# 007_Parallel_operation.net
KiCad netlist of a schematic drawn in Altium Designer
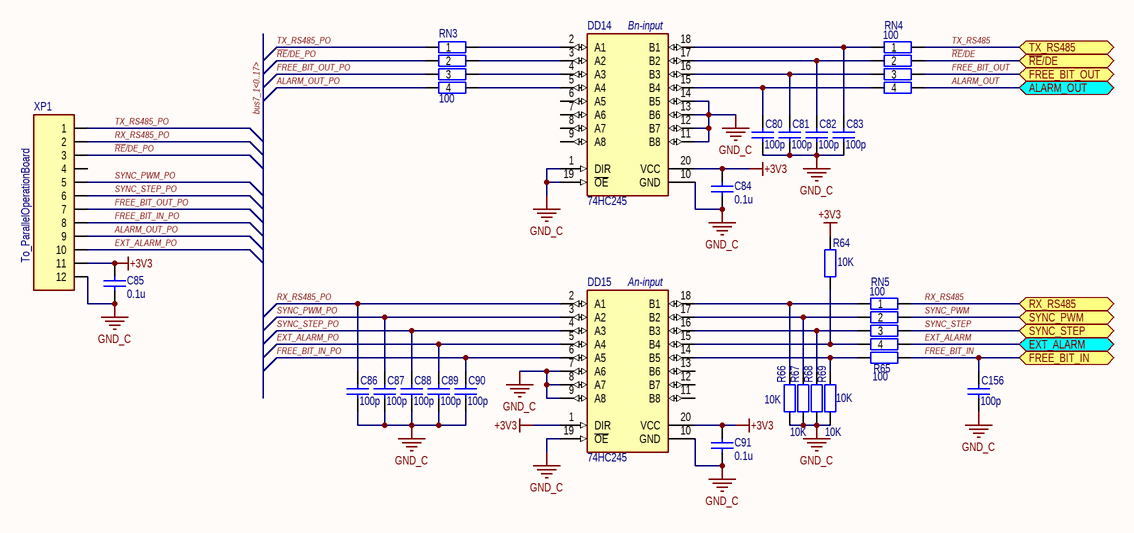
[diagram p0: 007_Parallel_operation.SchDoc]

(export (version "E")
  (design (tool "Eeschema 10.0.6"))
  (components
    (comp (ref "C80")
      (value "100p")
      (footprint "mainLib:SMD_C_0603")
      (description "SMD C 0603 MURATA 100V 5% NP0")
      (fields (field (name "PARTNUMBER") "GRM1885C2A101JA01") (field (name "MANUFACTURER") "MURATA"))
      (libsource (lib "mainRCLib") (part "C0603 100p 100V 5%"))
    )
    (comp (ref "C81")
      (value "100p")
      (footprint "mainLib:SMD_C_0603")
      (description "SMD C 0603 MURATA 100V 5% NP0")
      (fields (field (name "PARTNUMBER") "GRM1885C2A101JA01") (field (name "MANUFACTURER") "MURATA"))
      (libsource (lib "mainRCLib") (part "C0603 100p 100V 5%"))
    )
    (comp (ref "C82")
      (value "100p")
      (footprint "mainLib:SMD_C_0603")
      (description "SMD C 0603 MURATA 100V 5% NP0")
      (fields (field (name "PARTNUMBER") "GRM1885C2A101JA01") (field (name "MANUFACTURER") "MURATA"))
      (libsource (lib "mainRCLib") (part "C0603 100p 100V 5%"))
    )
    (comp (ref "C83")
      (value "100p")
      (footprint "mainLib:SMD_C_0603")
      (description "SMD C 0603 MURATA 100V 5% NP0")
      (fields (field (name "PARTNUMBER") "GRM1885C2A101JA01") (field (name "MANUFACTURER") "MURATA"))
      (libsource (lib "mainRCLib") (part "C0603 100p 100V 5%"))
    )
    (comp (ref "C84")
      (value "0.1u")
      (footprint "mainLib:SMD_C_0603")
      (description "SMD C 0603 MURATA 50V 10% X7R")
      (fields (field (name "PARTNUMBER") "GRM188R71H104K") (field (name "MANUFACTURER") "MURATA"))
      (libsource (lib "mainRCLib") (part "C0603 0.1u 50V 10%"))
    )
    (comp (ref "C85")
      (value "0.1u")
      (footprint "mainLib:SMD_C_0603")
      (description "SMD C 0603 MURATA 50V 10% X7R")
      (fields (field (name "PARTNUMBER") "GRM188R71H104K") (field (name "MANUFACTURER") "MURATA"))
      (libsource (lib "mainRCLib") (part "C0603 0.1u 50V 10%"))
    )
    (comp (ref "C86")
      (value "100p")
      (footprint "mainLib:SMD_C_0603")
      (description "SMD C 0603 MURATA 100V 5% NP0")
      (fields (field (name "PARTNUMBER") "GRM1885C2A101JA01") (field (name "MANUFACTURER") "MURATA"))
      (libsource (lib "mainRCLib") (part "C0603 100p 100V 5%"))
    )
    (comp (ref "C87")
      (value "100p")
      (footprint "mainLib:SMD_C_0603")
      (description "SMD C 0603 MURATA 100V 5% NP0")
      (fields (field (name "PARTNUMBER") "GRM1885C2A101JA01") (field (name "MANUFACTURER") "MURATA"))
      (libsource (lib "mainRCLib") (part "C0603 100p 100V 5%"))
    )
    (comp (ref "C88")
      (value "100p")
      (footprint "mainLib:SMD_C_0603")
      (description "SMD C 0603 MURATA 100V 5% NP0")
      (fields (field (name "PARTNUMBER") "GRM1885C2A101JA01") (field (name "MANUFACTURER") "MURATA"))
      (libsource (lib "mainRCLib") (part "C0603 100p 100V 5%"))
    )
    (comp (ref "C89")
      (value "100p")
      (footprint "mainLib:SMD_C_0603")
      (description "SMD C 0603 MURATA 100V 5% NP0")
      (fields (field (name "PARTNUMBER") "GRM1885C2A101JA01") (field (name "MANUFACTURER") "MURATA"))
      (libsource (lib "mainRCLib") (part "C0603 100p 100V 5%"))
    )
    (comp (ref "C90")
      (value "100p")
      (footprint "mainLib:SMD_C_0603")
      (description "SMD C 0603 MURATA 100V 5% NP0")
      (fields (field (name "PARTNUMBER") "GRM1885C2A101JA01") (field (name "MANUFACTURER") "MURATA"))
      (libsource (lib "mainRCLib") (part "C0603 100p 100V 5%"))
    )
    (comp (ref "C91")
      (value "0.1u")
      (footprint "mainLib:SMD_C_0603")
      (description "SMD C 0603 MURATA 50V 10% X7R")
      (fields (field (name "PARTNUMBER") "GRM188R71H104K") (field (name "MANUFACTURER") "MURATA"))
      (libsource (lib "mainRCLib") (part "C0603 0.1u 50V 10%"))
    )
    (comp (ref "C156")
      (value "100p")
      (footprint "mainLib:SMD_C_0603")
      (description "SMD C 0603 MURATA 100V 5% NP0")
      (fields (field (name "PARTNUMBER") "GRM1885C2A101JA01") (field (name "MANUFACTURER") "MURATA"))
      (libsource (lib "mainRCLib") (part "C0603 100p 100V 5%"))
    )
    (comp (ref "DD14")
      (value "74HC245")
      (footprint "mainLib:TSSOP20")
      (description "Octal Bus Transceivers With 3-State Outputs, PW0020A")
      (fields (field (name "MANUFACTURER") "Texas Instruments") (field (name "PARTNUMBER") "74HC245PW"))
      (libsource (lib "mainLib") (part "74HC245"))
    )
    (comp (ref "DD15")
      (value "74HC245")
      (footprint "mainLib:TSSOP20")
      (description "Octal Bus Transceivers With 3-State Outputs, PW0020A")
      (fields (field (name "MANUFACTURER") "Texas Instruments") (field (name "PARTNUMBER") "SN74HC245PW"))
      (libsource (lib "mainLib") (part "74HC245"))
    )
    (comp (ref "R64")
      (value "10K")
      (footprint "SMD_R_0603")
      (description "SMD R 0603 VISHAY 0.1W 75V 1% 100ppm")
      (fields (field (name "PARTNUMBER") "CRCW060310K0FK") (field (name "MANUFACTURER") "VISHAY"))
      (libsource (lib "mainRCLib") (part "R0603 10К 1%"))
    )
    (comp (ref "R65")
      (value "100")
      (footprint "SMD_R_0603")
      (description "SMD R 0603 VISHAY 0.1W 75V 1% 100ppm")
      (fields (field (name "PARTNUMBER") "CRCW0603100RFK") (field (name "MANUFACTURER") "VISHAY"))
      (libsource (lib "mainRCLib") (part "R0603 100 1%"))
    )
    (comp (ref "R66")
      (value "10K")
      (footprint "SMD_R_0603")
      (description "SMD R 0603 VISHAY 0.1W 75V 1% 100ppm")
      (fields (field (name "PARTNUMBER") "CRCW060310K0FK") (field (name "MANUFACTURER") "VISHAY"))
      (libsource (lib "mainRCLib") (part "R0603 10К 1%"))
    )
    (comp (ref "R67")
      (value "10K")
      (footprint "SMD_R_0603")
      (description "SMD R 0603 VISHAY 0.1W 75V 1% 100ppm")
      (fields (field (name "PARTNUMBER") "CRCW060310K0FK") (field (name "MANUFACTURER") "VISHAY"))
      (libsource (lib "mainRCLib") (part "R0603 10К 1%"))
    )
    (comp (ref "R68")
      (value "10K")
      (footprint "SMD_R_0603")
      (description "SMD R 0603 VISHAY 0.1W 75V 1% 100ppm")
      (fields (field (name "PARTNUMBER") "CRCW060310K0FK") (field (name "MANUFACTURER") "VISHAY"))
      (libsource (lib "mainRCLib") (part "R0603 10К 1%"))
    )
    (comp (ref "R69")
      (value "10K")
      (footprint "SMD_R_0603")
      (description "SMD R 0603 VISHAY 0.1W 75V 1% 100ppm")
      (fields (field (name "PARTNUMBER") "CRCW060310K0FK") (field (name "MANUFACTURER") "VISHAY"))
      (libsource (lib "mainRCLib") (part "R0603 10К 1%"))
    )
    (comp (ref "RN3")
      (value "100")
      (footprint "mainLib:CRA06S")
      (description "SMD RESISTOR ARRAY VISHAY 0.063W 50V 1% 100ppm")
      (fields (field (name "PARTNUMBER") "CRA06S083100RF") (field (name "MANUFACTURER") "VISHAY"))
      (libsource (lib "mainRCLib") (part "CRA06S 4x100 1%"))
    )
    (comp (ref "RN4")
      (value "100")
      (footprint "mainLib:CRA06S")
      (description "SMD RESISTOR ARRAY VISHAY 0.063W 50V 1% 100ppm")
      (fields (field (name "PARTNUMBER") "CRA06S083100RF") (field (name "MANUFACTURER") "VISHAY"))
      (libsource (lib "mainRCLib") (part "CRA06S 4x100 1%"))
    )
    (comp (ref "RN5")
      (value "100")
      (footprint "mainLib:CRA06S")
      (description "SMD RESISTOR ARRAY VISHAY 0.063W 50V 1% 100ppm")
      (fields (field (name "PARTNUMBER") "CRA06S083100RF") (field (name "MANUFACTURER") "VISHAY"))
      (libsource (lib "mainRCLib") (part "CRA06S 4x100 1%"))
    )
    (comp (ref "XP1")
      (value "То_ParallelOperationBoard")
      (footprint "mainLib:XP(ParallelOperation)")
      (description "to ParallelOperationBoard")
      (fields (field (name "PARTNUMBER") "R100.20.62.10.00") (field (name "MANUFACTURER") "OLTEST"))
      (libsource (lib "mainLib") (part "Plata_ParallelOperation"))
    )
  )
  (nets
    (net (code "2") (name "+3V3") (class "Default")
      (node (ref "C84") (pin "2") (pinfunction "2_2") (pintype "passive"))
      (node (ref "C85") (pin "2") (pinfunction "2_2") (pintype "passive"))
      (node (ref "C91") (pin "2") (pinfunction "2_2") (pintype "passive"))
      (node (ref "DD14") (pin "20") (pinfunction "VCC_20") (pintype "power_in"))
      (node (ref "DD15") (pin "1") (pinfunction "DIR_1") (pintype "input"))
      (node (ref "DD15") (pin "20") (pinfunction "VCC_20") (pintype "power_in"))
      (node (ref "R64") (pin "2") (pinfunction "2_2") (pintype "passive"))
      (node (ref "XP1") (pin "11") (pinfunction "11_11") (pintype "passive"))
    )
    (net (code "3") (name "/ALARM_OUT") (class "Default")
      (node (ref "RN4") (pin "5") (pinfunction "5_5") (pintype "passive"))
    )
    (net (code "4") (name "/ALARM_OUT_PO") (class "Default")
      (node (ref "RN3") (pin "4") (pinfunction "4_4") (pintype "passive"))
      (node (ref "XP1") (pin "9") (pinfunction "9_9") (pintype "passive"))
    )
    (net (code "5") (name "/EXT_ALARM") (class "Default")
      (node (ref "RN5") (pin "5") (pinfunction "5_5") (pintype "passive"))
    )
    (net (code "6") (name "/EXT_ALARM_PO") (class "Default")
      (node (ref "C89") (pin "2") (pinfunction "2_2") (pintype "passive"))
      (node (ref "DD15") (pin "5") (pinfunction "A4_5") (pintype "bidirectional"))
      (node (ref "XP1") (pin "10") (pinfunction "10_10") (pintype "passive"))
    )
    (net (code "7") (name "/FREE_BIT_IN") (class "Default")
      (node (ref "C156") (pin "2") (pinfunction "2_2") (pintype "passive"))
      (node (ref "R65") (pin "2") (pinfunction "2_2") (pintype "passive"))
    )
    (net (code "8") (name "/FREE_BIT_IN_PO") (class "Default")
      (node (ref "C90") (pin "2") (pinfunction "2_2") (pintype "passive"))
      (node (ref "DD15") (pin "6") (pinfunction "A5_6") (pintype "bidirectional"))
      (node (ref "XP1") (pin "8") (pinfunction "8_8") (pintype "passive"))
    )
    (net (code "9") (name "/FREE_BIT_OUT") (class "Default")
      (node (ref "RN4") (pin "6") (pinfunction "6_6") (pintype "passive"))
    )
    (net (code "10") (name "/FREE_BIT_OUT_PO") (class "Default")
      (node (ref "RN3") (pin "3") (pinfunction "3_3") (pintype "passive"))
      (node (ref "XP1") (pin "7") (pinfunction "7_7") (pintype "passive"))
    )
    (net (code "11") (name "/RX_RS485") (class "Default")
      (node (ref "RN5") (pin "8") (pinfunction "8_8") (pintype "passive"))
    )
    (net (code "12") (name "/RX_RS485_PO") (class "Default")
      (node (ref "C86") (pin "2") (pinfunction "2_2") (pintype "passive"))
      (node (ref "DD15") (pin "2") (pinfunction "A1_2") (pintype "bidirectional"))
      (node (ref "XP1") (pin "2") (pinfunction "2_2") (pintype "passive"))
    )
    (net (code "13") (name "/SYNC_PWM") (class "Default")
      (node (ref "RN5") (pin "7") (pinfunction "7_7") (pintype "passive"))
    )
    (net (code "14") (name "/SYNC_PWM_PO") (class "Default")
      (node (ref "C87") (pin "2") (pinfunction "2_2") (pintype "passive"))
      (node (ref "DD15") (pin "3") (pinfunction "A2_3") (pintype "bidirectional"))
      (node (ref "XP1") (pin "5") (pinfunction "5_5") (pintype "passive"))
    )
    (net (code "15") (name "/SYNC_STEP") (class "Default")
      (node (ref "RN5") (pin "6") (pinfunction "6_6") (pintype "passive"))
    )
    (net (code "16") (name "/SYNC_STEP_PO") (class "Default")
      (node (ref "C88") (pin "2") (pinfunction "2_2") (pintype "passive"))
      (node (ref "DD15") (pin "4") (pinfunction "A3_4") (pintype "bidirectional"))
      (node (ref "XP1") (pin "6") (pinfunction "6_6") (pintype "passive"))
    )
    (net (code "17") (name "/TX_RS485") (class "Default")
      (node (ref "RN4") (pin "8") (pinfunction "8_8") (pintype "passive"))
    )
    (net (code "18") (name "/TX_RS485_PO") (class "Default")
      (node (ref "RN3") (pin "1") (pinfunction "1_1") (pintype "passive"))
      (node (ref "XP1") (pin "1") (pinfunction "1_1") (pintype "passive"))
    )
    (net (code "20") (name "/~{RE}{slash}DE") (class "Default")
      (node (ref "RN4") (pin "7") (pinfunction "7_7") (pintype "passive"))
    )
    (net (code "21") (name "/~{RE}{slash}DE_PO") (class "Default")
      (node (ref "RN3") (pin "2") (pinfunction "2_2") (pintype "passive"))
      (node (ref "XP1") (pin "3") (pinfunction "3_3") (pintype "passive"))
    )
    (net (code "22") (name "GND_C") (class "Default")
      (node (ref "C156") (pin "1") (pinfunction "1_1") (pintype "passive"))
      (node (ref "C80") (pin "1") (pinfunction "1_1") (pintype "passive"))
      (node (ref "C81") (pin "1") (pinfunction "1_1") (pintype "passive"))
      (node (ref "C82") (pin "1") (pinfunction "1_1") (pintype "passive"))
      (node (ref "C83") (pin "1") (pinfunction "1_1") (pintype "passive"))
      (node (ref "C84") (pin "1") (pinfunction "1_1") (pintype "passive"))
      (node (ref "C85") (pin "1") (pinfunction "1_1") (pintype "passive"))
      (node (ref "C86") (pin "1") (pinfunction "1_1") (pintype "passive"))
      (node (ref "C87") (pin "1") (pinfunction "1_1") (pintype "passive"))
      (node (ref "C88") (pin "1") (pinfunction "1_1") (pintype "passive"))
      (node (ref "C89") (pin "1") (pinfunction "1_1") (pintype "passive"))
      (node (ref "C90") (pin "1") (pinfunction "1_1") (pintype "passive"))
      (node (ref "C91") (pin "1") (pinfunction "1_1") (pintype "passive"))
      (node (ref "DD14") (pin "1") (pinfunction "DIR_1") (pintype "input"))
      (node (ref "DD14") (pin "10") (pinfunction "GND_10") (pintype "power_in"))
      (node (ref "DD14") (pin "11") (pinfunction "B8_11") (pintype "bidirectional"))
      (node (ref "DD14") (pin "12") (pinfunction "B7_12") (pintype "bidirectional"))
      (node (ref "DD14") (pin "13") (pinfunction "B6_13") (pintype "bidirectional"))
      (node (ref "DD14") (pin "14") (pinfunction "B5_14") (pintype "bidirectional"))
      (node (ref "DD14") (pin "19") (pinfunction "~{OE}_19") (pintype "input"))
      (node (ref "DD15") (pin "10") (pinfunction "GND_10") (pintype "power_in"))
      (node (ref "DD15") (pin "19") (pinfunction "~{OE}_19") (pintype "input"))
      (node (ref "DD15") (pin "7") (pinfunction "A6_7") (pintype "bidirectional"))
      (node (ref "DD15") (pin "8") (pinfunction "A7_8") (pintype "bidirectional"))
      (node (ref "DD15") (pin "9") (pinfunction "A8_9") (pintype "bidirectional"))
      (node (ref "R66") (pin "1") (pinfunction "1_1") (pintype "passive"))
      (node (ref "R67") (pin "1") (pinfunction "1_1") (pintype "passive"))
      (node (ref "R68") (pin "1") (pinfunction "1_1") (pintype "passive"))
      (node (ref "R69") (pin "1") (pinfunction "1_1") (pintype "passive"))
      (node (ref "XP1") (pin "12") (pinfunction "12_12") (pintype "passive"))
    )
    (net (code "23") (name "Net-(DD14-A1)") (class "Default")
      (node (ref "DD14") (pin "2") (pinfunction "A1_2") (pintype "bidirectional"))
      (node (ref "RN3") (pin "8") (pinfunction "8_8") (pintype "passive"))
    )
    (net (code "24") (name "Net-(DD14-A2)") (class "Default")
      (node (ref "DD14") (pin "3") (pinfunction "A2_3") (pintype "bidirectional"))
      (node (ref "RN3") (pin "7") (pinfunction "7_7") (pintype "passive"))
    )
    (net (code "25") (name "Net-(DD14-A3)") (class "Default")
      (node (ref "DD14") (pin "4") (pinfunction "A3_4") (pintype "bidirectional"))
      (node (ref "RN3") (pin "6") (pinfunction "6_6") (pintype "passive"))
    )
    (net (code "26") (name "Net-(DD14-A4)") (class "Default")
      (node (ref "DD14") (pin "5") (pinfunction "A4_5") (pintype "bidirectional"))
      (node (ref "RN3") (pin "5") (pinfunction "5_5") (pintype "passive"))
    )
    (net (code "27") (name "Net-(DD14-B1)") (class "Default")
      (node (ref "C83") (pin "2") (pinfunction "2_2") (pintype "passive"))
      (node (ref "DD14") (pin "18") (pinfunction "B1_18") (pintype "bidirectional"))
      (node (ref "RN4") (pin "1") (pinfunction "1_1") (pintype "passive"))
    )
    (net (code "28") (name "Net-(DD14-B2)") (class "Default")
      (node (ref "C82") (pin "2") (pinfunction "2_2") (pintype "passive"))
      (node (ref "DD14") (pin "17") (pinfunction "B2_17") (pintype "bidirectional"))
      (node (ref "RN4") (pin "2") (pinfunction "2_2") (pintype "passive"))
    )
    (net (code "29") (name "Net-(DD14-B3)") (class "Default")
      (node (ref "C81") (pin "2") (pinfunction "2_2") (pintype "passive"))
      (node (ref "DD14") (pin "16") (pinfunction "B3_16") (pintype "bidirectional"))
      (node (ref "RN4") (pin "3") (pinfunction "3_3") (pintype "passive"))
    )
    (net (code "30") (name "Net-(DD14-B4)") (class "Default")
      (node (ref "C80") (pin "2") (pinfunction "2_2") (pintype "passive"))
      (node (ref "DD14") (pin "15") (pinfunction "B4_15") (pintype "bidirectional"))
      (node (ref "RN4") (pin "4") (pinfunction "4_4") (pintype "passive"))
    )
    (net (code "31") (name "Net-(DD15-B1)") (class "Default")
      (node (ref "DD15") (pin "18") (pinfunction "B1_18") (pintype "bidirectional"))
      (node (ref "R66") (pin "2") (pinfunction "2_2") (pintype "passive"))
      (node (ref "RN5") (pin "1") (pinfunction "1_1") (pintype "passive"))
    )
    (net (code "32") (name "Net-(DD15-B2)") (class "Default")
      (node (ref "DD15") (pin "17") (pinfunction "B2_17") (pintype "bidirectional"))
      (node (ref "R67") (pin "2") (pinfunction "2_2") (pintype "passive"))
      (node (ref "RN5") (pin "2") (pinfunction "2_2") (pintype "passive"))
    )
    (net (code "33") (name "Net-(DD15-B3)") (class "Default")
      (node (ref "DD15") (pin "16") (pinfunction "B3_16") (pintype "bidirectional"))
      (node (ref "R68") (pin "2") (pinfunction "2_2") (pintype "passive"))
      (node (ref "RN5") (pin "3") (pinfunction "3_3") (pintype "passive"))
    )
    (net (code "34") (name "Net-(DD15-B4)") (class "Default")
      (node (ref "DD15") (pin "15") (pinfunction "B4_15") (pintype "bidirectional"))
      (node (ref "R64") (pin "1") (pinfunction "1_1") (pintype "passive"))
      (node (ref "RN5") (pin "4") (pinfunction "4_4") (pintype "passive"))
    )
    (net (code "35") (name "Net-(DD15-B5)") (class "Default")
      (node (ref "DD15") (pin "14") (pinfunction "B5_14") (pintype "bidirectional"))
      (node (ref "R65") (pin "1") (pinfunction "1_1") (pintype "passive"))
      (node (ref "R69") (pin "2") (pinfunction "2_2") (pintype "passive"))
    )
    (net (code "36") (name "unconnected-(DD14-A5-Pad6)") (class "Default")
      (node (ref "DD14") (pin "6") (pinfunction "A5_6") (pintype "bidirectional"))
    )
    (net (code "37") (name "unconnected-(DD14-A6-Pad7)") (class "Default")
      (node (ref "DD14") (pin "7") (pinfunction "A6_7") (pintype "bidirectional"))
    )
    (net (code "38") (name "unconnected-(DD14-A7-Pad8)") (class "Default")
      (node (ref "DD14") (pin "8") (pinfunction "A7_8") (pintype "bidirectional"))
    )
    (net (code "39") (name "unconnected-(DD14-A8-Pad9)") (class "Default")
      (node (ref "DD14") (pin "9") (pinfunction "A8_9") (pintype "bidirectional"))
    )
    (net (code "40") (name "unconnected-(DD15-B6-Pad13)") (class "Default")
      (node (ref "DD15") (pin "13") (pinfunction "B6_13") (pintype "bidirectional"))
    )
    (net (code "41") (name "unconnected-(DD15-B7-Pad12)") (class "Default")
      (node (ref "DD15") (pin "12") (pinfunction "B7_12") (pintype "bidirectional"))
    )
    (net (code "42") (name "unconnected-(DD15-B8-Pad11)") (class "Default")
      (node (ref "DD15") (pin "11") (pinfunction "B8_11") (pintype "bidirectional"))
    )
    (net (code "43") (name "unconnected-(XP1-Pad4)") (class "Default")
      (node (ref "XP1") (pin "4") (pinfunction "4_4") (pintype "passive"))
    )
  )
)
